# Qunyin_mmWave_flash_USB.net
KiCad netlist of a schematic drawn in Altium Designer
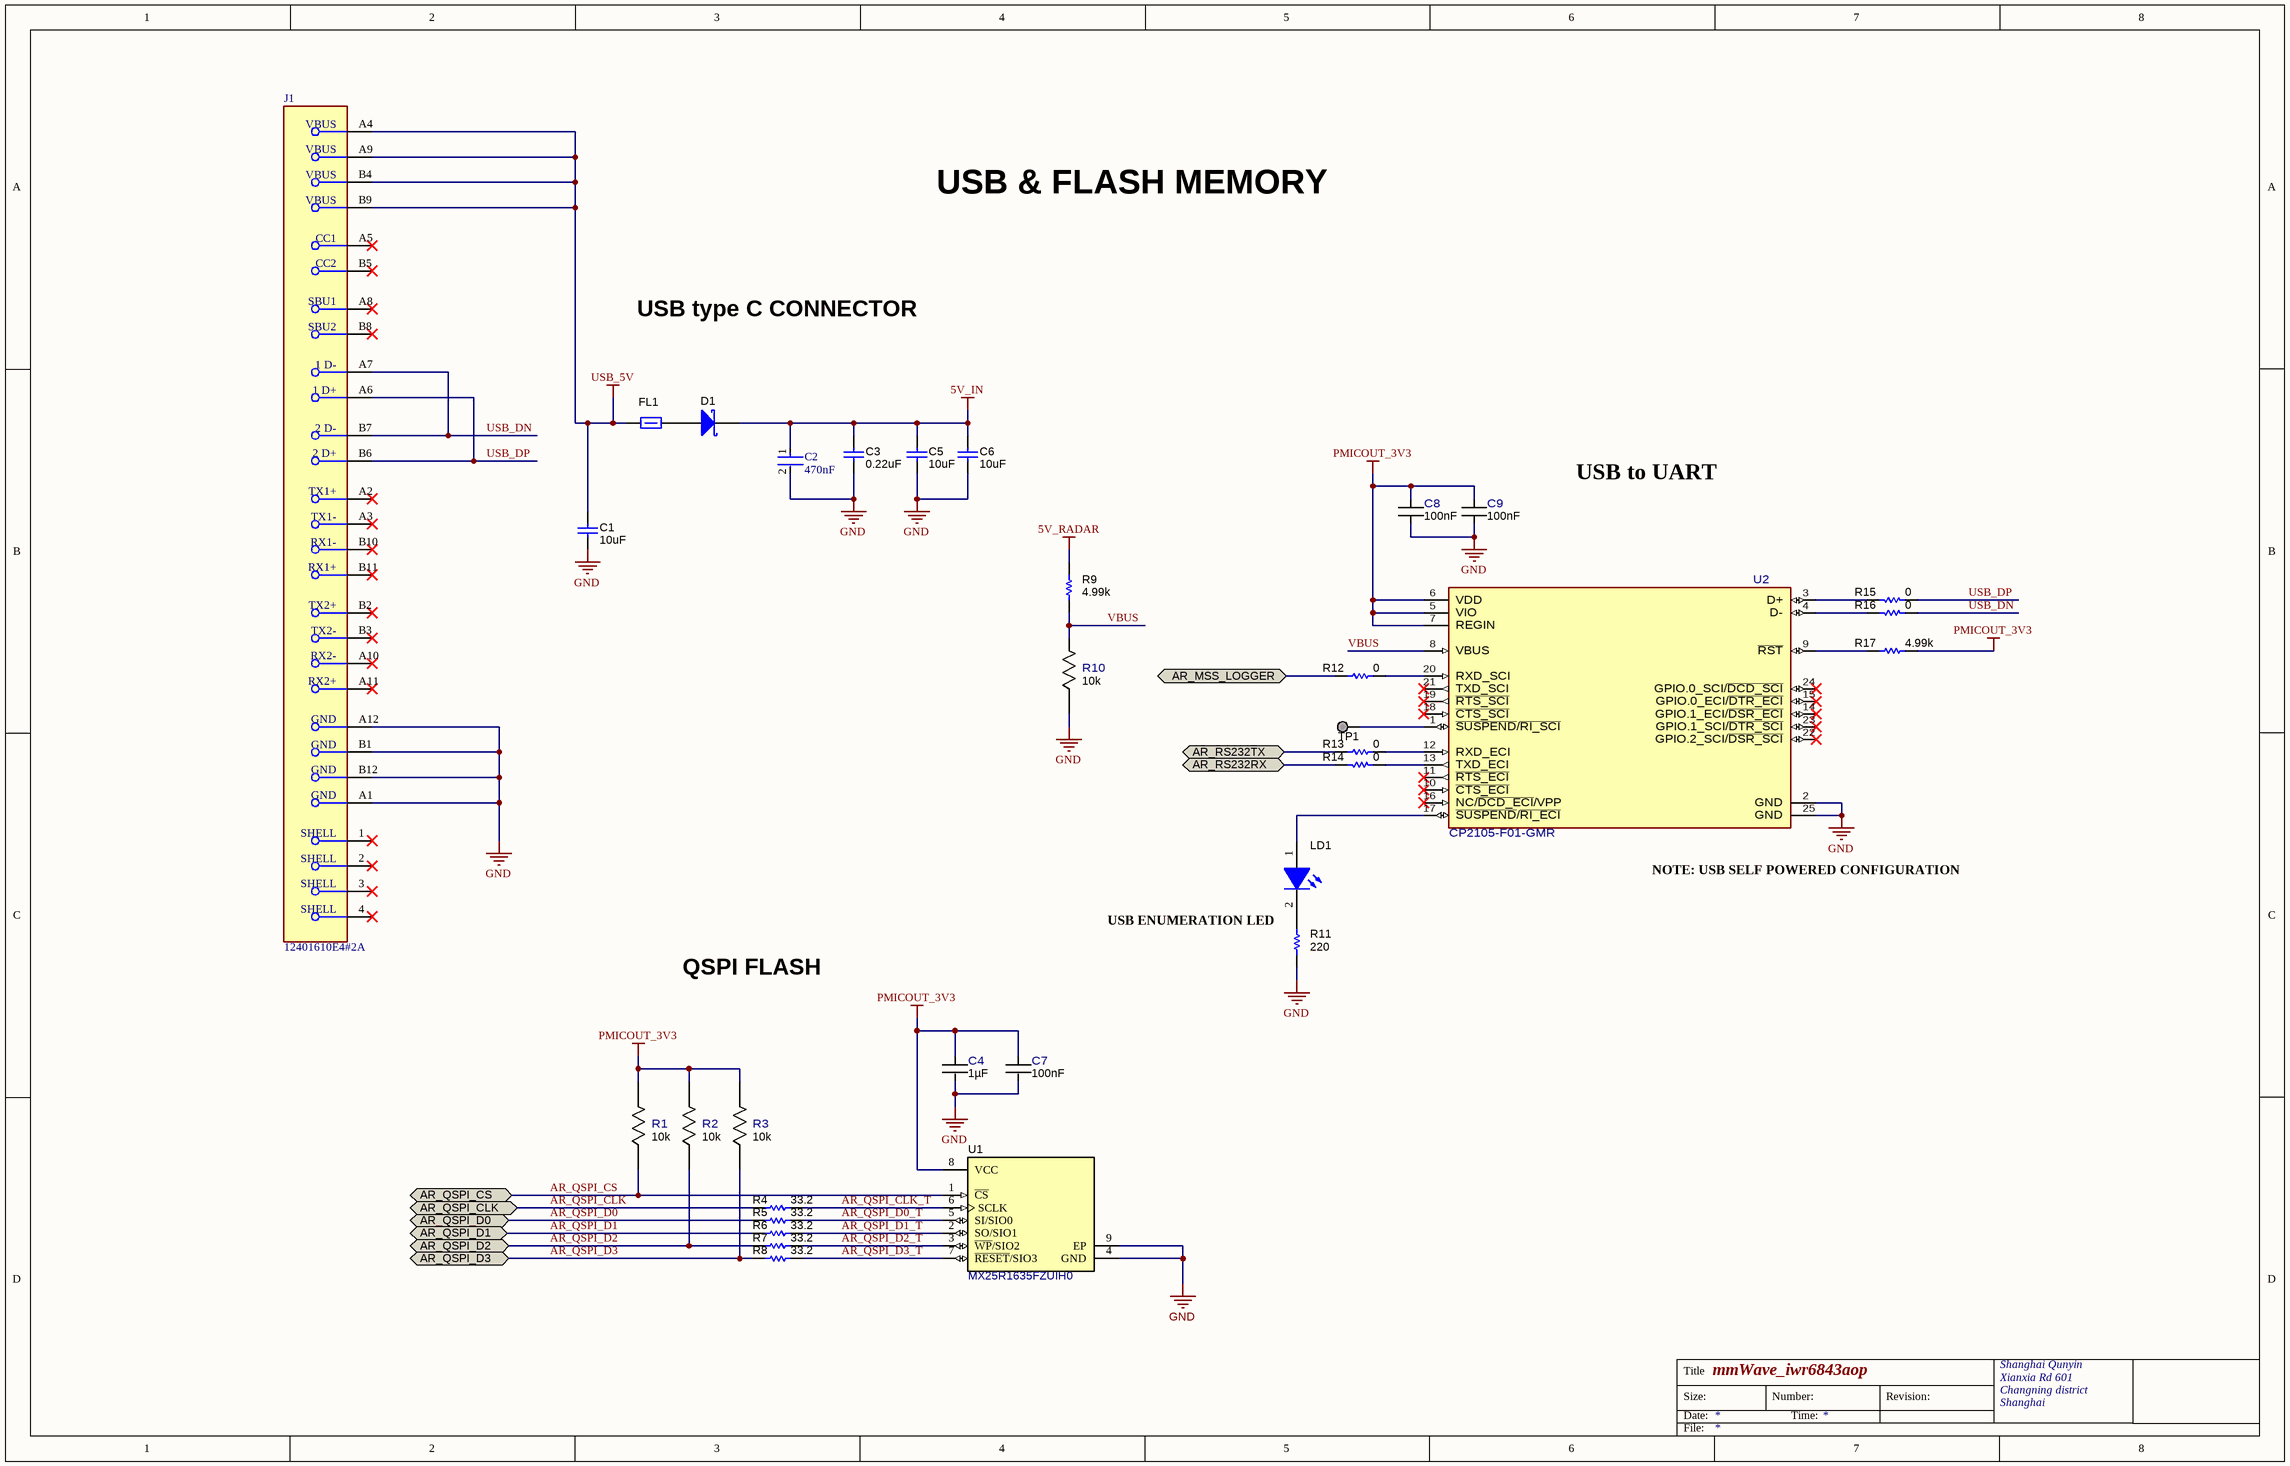
[diagram p0: Qunyin_mmWave_flash&USB.SchDoc]

(export (version "E")
  (design (tool "Eeschema 10.0.6"))
  (components
    (comp (ref "C1")
      (value "10uF")
      (footprint "0402_070")
      (description "CAP, CERM, 10 uF, 10 V, +/- 20%, X5R, 0402")
      (fields
        (field (name "MANUFACTURER") "Samsung Electro-Mechanics")
        (field (name "PARTNUMBER") "CL05A106MP5NUNC")
      )
      (libsource (lib "Altium Vault - TI") (part "Capacitor"))
    )
    (comp (ref "C2")
      (value "C1005X5R1E474K050BB")
      (footprint "FP-C1005-050-0_05-IPC_B")
      (description "Multilayer Ceramic Capacitors 470nF ±10% 25V X5R SMD 0402")
      (fields
        (field (name "VOLTAGE") "25V")
        (field (name "TOLERANCE") "10%")
        (field (name "CAPACITANCE") "470nF")
      )
      (libsource (lib "Altium Content Vault") (part "b4654b650e69147ec39a6b967a45e02"))
    )
    (comp (ref "C3")
      (value "0.22uF")
      (footprint "0201_033L")
      (description "CAP, CERM, 0.22 uF, 10 V, +/- 20%, X5R, 0201")
      (fields
        (field (name "MANUFACTURER") "Taiyo Yuden")
        (field (name "PARTNUMBER") "LMK063BJ224MP-F")
        (field (name "PUBLISHER") "Texas Instruments")
      )
      (libsource (lib "Altium Vault - TI") (part "Capacitor"))
    )
    (comp (ref "C4")
      (value "CL03A105MO3NRNH")
      (footprint "FP-CL03A105MO3NRNH_0201-IPC_C")
      (description "1µF ±20% 16V Ceramic Capacitor X5R 0201")
      (fields (field (name "CAP_F") "1µF") (field (name "MANUFACTURER") "Samsung Electro-Mechanics"))
      (libsource (lib "Altium Vault - TI") (part "SYM-B32642B0223J"))
    )
    (comp (ref "C5")
      (value "10uF")
      (footprint "0402_070")
      (description "CAP, CERM, 10 uF, 10 V, +/- 20%, X5R, 0402")
      (fields
        (field (name "MANUFACTURER") "Samsung Electro-Mechanics")
        (field (name "PARTNUMBER") "CL05A106MP5NUNC")
      )
      (libsource (lib "Altium Vault - TI") (part "Capacitor"))
    )
    (comp (ref "C6")
      (value "10uF")
      (footprint "0402_070")
      (description "CAP, CERM, 10 uF, 10 V, +/- 20%, X5R, 0402")
      (fields
        (field (name "MANUFACTURER") "Samsung Electro-Mechanics")
        (field (name "PARTNUMBER") "CL05A106MP5NUNC")
      )
      (libsource (lib "Altium Vault - TI") (part "Capacitor"))
    )
    (comp (ref "C7")
      (value "GRM033R6YA104KE14D")
      (footprint "FP-GRM033R6YA104KE14D_0201 (0603 Metric)-IPC_C")
      (description "Cap Ceramic 0.1uF 35V X5R 10% Pad SMD 0201 85C T/R")
      (fields (field (name "CAP_F") "100nF") (field (name "MANUFACTURER") "Murata Electronics North America"))
      (libsource (lib "Altium Vault - TI") (part "SYM-B32642B0223J"))
    )
    (comp (ref "C8")
      (value "GRM033R6YA104KE14D")
      (footprint "FP-GRM033R6YA104KE14D_0201 (0603 Metric)-IPC_C")
      (description "Cap Ceramic 0.1uF 35V X5R 10% Pad SMD 0201 85C T/R")
      (fields (field (name "CAP_F") "100nF") (field (name "MANUFACTURER") "Murata Electronics North America"))
      (libsource (lib "Altium Vault - TI") (part "SYM-B32642B0223J"))
    )
    (comp (ref "C9")
      (value "GRM033R6YA104KE14D")
      (footprint "FP-GRM033R6YA104KE14D_0201 (0603 Metric)-IPC_C")
      (description "Cap Ceramic 0.1uF 35V X5R 10% Pad SMD 0201 85C T/R")
      (fields (field (name "CAP_F") "100nF") (field (name "MANUFACTURER") "Murata Electronics North America"))
      (libsource (lib "Altium Vault - TI") (part "SYM-B32642B0223J"))
    )
    (comp (ref "D1")
      (value "NSR20F30NXT5G")
      (footprint "DSN2_0603")
      (description "Diode, Schottky, 30 V, 2 A, 2-XFDFN")
      (fields (field (name "MANUFACTURER") "ON Semiconductor"))
      (libsource (lib "Altium Vault - TI") (part "DIODE_SCHOTTKY"))
    )
    (comp (ref "FL1")
      (value "BLM15PD300SZ1D")
      (footprint "0402L")
      (description "Inductor, Ferrite Bead, Ferrite, 2.2 A, 0.035 ohm, AEC-Q200 Grade 1, SMD")
      (fields (field (name "MANUFACTURER") "MuRata") (field (name "PUBLISHER") "Texas Instruments"))
      (libsource (lib "Altium Vault - TI") (part "Ferrite_Bead"))
    )
    (comp (ref "J1")
      (value "12401610E4#2A")
      (footprint "FP-12401610E4#2A-MFG")
      (description "CONN RCP USB3.1 TYPEC 24P SMD RA")
      (libsource (lib "Altium Content Vault") (part "7c76f4c47d7e2af8b8797da79635f2a"))
    )
    (comp (ref "LD1")
      (value "APHHS1005CGCK")
      (footprint "APHHS1005_Green")
      (description "LED, Green, SMD")
      (fields (field (name "MANUFACTURER") "Kingbright"))
      (libsource (lib "Altium Vault - TI") (part "LED"))
    )
    (comp (ref "R1")
      (value "RR0306P-103-D")
      (footprint "FP-RR0306P-103-D_0201-IPC_C")
      (description "10 kOhms ±0.5% 0.05W, 1/20W Chip Resistor 0201 (0603 Metric)  Thin Film")
      (fields (field (name "MANUFACTURER") "Susumu") (field (name "RES_OHM") "10k"))
      (libsource (lib "Altium Vault - TI") (part "SYM-PMR18EZPJ000"))
    )
    (comp (ref "R2")
      (value "RR0306P-103-D")
      (footprint "FP-RR0306P-103-D_0201-IPC_C")
      (description "10 kOhms ±0.5% 0.05W, 1/20W Chip Resistor 0201 (0603 Metric)  Thin Film")
      (fields (field (name "MANUFACTURER") "Susumu") (field (name "RES_OHM") "10k"))
      (libsource (lib "Altium Vault - TI") (part "SYM-PMR18EZPJ000"))
    )
    (comp (ref "R3")
      (value "RR0306P-103-D")
      (footprint "FP-RR0306P-103-D_0201-IPC_C")
      (description "10 kOhms ±0.5% 0.05W, 1/20W Chip Resistor 0201 (0603 Metric)  Thin Film")
      (fields (field (name "MANUFACTURER") "Susumu") (field (name "RES_OHM") "10k"))
      (libsource (lib "Altium Vault - TI") (part "SYM-PMR18EZPJ000"))
    )
    (comp (ref "R4")
      (value "33.2")
      (footprint "0201L")
      (description "RES, 33.2, 1%, 0.05 W, 0201")
      (fields (field (name "MANUFACTURER") "Vishay-Dale") (field (name "PARTNUMBER") "CRCW020133R2FNED"))
      (libsource (lib "Altium Vault - TI") (part "Resistor"))
    )
    (comp (ref "R5")
      (value "33.2")
      (footprint "0201L")
      (description "RES, 33.2, 1%, 0.05 W, 0201")
      (fields (field (name "MANUFACTURER") "Vishay-Dale") (field (name "PARTNUMBER") "CRCW020133R2FNED"))
      (libsource (lib "Altium Vault - TI") (part "Resistor"))
    )
    (comp (ref "R6")
      (value "33.2")
      (footprint "0201L")
      (description "RES, 33.2, 1%, 0.05 W, 0201")
      (fields (field (name "MANUFACTURER") "Vishay-Dale") (field (name "PARTNUMBER") "CRCW020133R2FNED"))
      (libsource (lib "Altium Vault - TI") (part "Resistor"))
    )
    (comp (ref "R7")
      (value "33.2")
      (footprint "0201L")
      (description "RES, 33.2, 1%, 0.05 W, 0201")
      (fields (field (name "MANUFACTURER") "Vishay-Dale") (field (name "PARTNUMBER") "CRCW020133R2FNED"))
      (libsource (lib "Altium Vault - TI") (part "Resistor"))
    )
    (comp (ref "R8")
      (value "33.2")
      (footprint "0201L")
      (description "RES, 33.2, 1%, 0.05 W, 0201")
      (fields (field (name "MANUFACTURER") "Vishay-Dale") (field (name "PARTNUMBER") "CRCW020133R2FNED"))
      (libsource (lib "Altium Vault - TI") (part "Resistor"))
    )
    (comp (ref "R9")
      (value "4.99k")
      (footprint "0201L")
      (description "RES, 4.99 k, 1%, 0.05 W, 0201")
      (fields
        (field (name "MANUFACTURER") "Yageo America")
        (field (name "PARTNUMBER") "RC0201FR-074K99L")
        (field (name "PUBLISHER") "Texas Instruments")
      )
      (libsource (lib "Altium Vault - TI") (part "Resistor"))
    )
    (comp (ref "R10")
      (value "RR0306P-103-D")
      (footprint "FP-RR0306P-103-D_0201-IPC_C")
      (description "10 kOhms ±0.5% 0.05W, 1/20W Chip Resistor 0201 (0603 Metric)  Thin Film")
      (fields (field (name "MANUFACTURER") "Susumu") (field (name "RES_OHM") "10k"))
      (libsource (lib "Altium Vault - TI") (part "SYM-PMR18EZPJ000"))
    )
    (comp (ref "R11")
      (value "220")
      (footprint "0201L")
      (description "RES, 220, 5%, 0.05 W, 0201")
      (fields
        (field (name "MANUFACTURER") "Yageo America")
        (field (name "PARTNUMBER") "RC0201JR-07220RL")
        (field (name "PUBLISHER") "Texas Instruments")
      )
      (libsource (lib "Altium Vault - TI") (part "Resistor"))
    )
    (comp (ref "R12")
      (value "RC0201JR-070RL")
      (footprint "FP-RC0201JR-070RL_0201 (0603 Metric)-MFG")
      (description "RES SMD 0 OHM JUMPER 1/20W 0201")
      (fields (field (name "MANUFACTURER") "Yageo") (field (name "RES_OHM") "0"))
      (libsource (lib "Altium Vault - TI") (part "SYM-WSR3R1500F"))
    )
    (comp (ref "R13")
      (value "RC0201JR-070RL")
      (footprint "FP-RC0201JR-070RL_0201 (0603 Metric)-MFG")
      (description "RES SMD 0 OHM JUMPER 1/20W 0201")
      (fields (field (name "MANUFACTURER") "Yageo") (field (name "RES_OHM") "0"))
      (libsource (lib "Altium Vault - TI") (part "SYM-WSR3R1500F"))
    )
    (comp (ref "R14")
      (value "RC0201JR-070RL")
      (footprint "FP-RC0201JR-070RL_0201 (0603 Metric)-MFG")
      (description "RES SMD 0 OHM JUMPER 1/20W 0201")
      (fields (field (name "MANUFACTURER") "Yageo") (field (name "RES_OHM") "0"))
      (libsource (lib "Altium Vault - TI") (part "SYM-WSR3R1500F"))
    )
    (comp (ref "R15")
      (value "RC0201JR-070RL")
      (footprint "FP-RC0201JR-070RL_0201 (0603 Metric)-MFG")
      (description "RES SMD 0 OHM JUMPER 1/20W 0201")
      (fields (field (name "MANUFACTURER") "Yageo") (field (name "RES_OHM") "0"))
      (libsource (lib "Altium Vault - TI") (part "SYM-WSR3R1500F"))
    )
    (comp (ref "R16")
      (value "RC0201JR-070RL")
      (footprint "FP-RC0201JR-070RL_0201 (0603 Metric)-MFG")
      (description "RES SMD 0 OHM JUMPER 1/20W 0201")
      (fields (field (name "MANUFACTURER") "Yageo") (field (name "RES_OHM") "0"))
      (libsource (lib "Altium Vault - TI") (part "SYM-WSR3R1500F"))
    )
    (comp (ref "R17")
      (value "4.99k")
      (footprint "0201L")
      (description "RES, 4.99 k, 1%, 0.05 W, 0201")
      (fields
        (field (name "MANUFACTURER") "Yageo America")
        (field (name "PARTNUMBER") "RC0201FR-074K99L")
        (field (name "PUBLISHER") "Texas Instruments")
      )
      (libsource (lib "Altium Vault - TI") (part "Resistor"))
    )
    (comp (ref "TP1")
      (value "TESTPOINT")
      (footprint "TP_25MIL-SMT")
      (description "TEST POINT.  No entry in BOM.")
      (libsource (lib "Altium Vault - TI") (part "TESTPOINT"))
    )
    (comp (ref "U1")
      (value "MX25R1635FZUIH0")
      (footprint "USON-8L")
      (description "ULTRA LOW POWER, 16M-BIT [x 1/x 2/x 4] CMOS MXSMIO (SERIAL MULTI I/O) FLASH MEMORY, SON-8")
      (fields (field (name "MANUFACTURER") "Macronix International Co., LTD"))
      (libsource (lib "Altium Vault - TI") (part "MX25R1635FZNIH"))
    )
    (comp (ref "U2")
      (value "CP2105-F01-GMR")
      (footprint "FP-CP2105-F01-GMR_QFN24-EP-IPC_A")
      (description "I/O Controller Interface IC USB to Dual UART bridge")
      (fields (field (name "MANUFACTURER") "Silicon Labs"))
      (libsource (lib "Altium Vault - TI") (part "SYM-CP2105-F01-GMR"))
    )
  )
  (nets
    (net (code "1") (name "/AR_MSS_LOGGER") (class "Default")
      (node (ref "R12") (pin "2") (pinfunction "2_2") (pintype "passive"))
    )
    (net (code "2") (name "/AR_QSPI_CLK") (class "Default")
      (node (ref "R4") (pin "1") (pinfunction "1_1") (pintype "passive"))
    )
    (net (code "3") (name "/AR_QSPI_CLK_T") (class "Default")
      (node (ref "R4") (pin "2") (pinfunction "2_2") (pintype "passive"))
      (node (ref "U1") (pin "6") (pinfunction "SCLK_6") (pintype "input"))
    )
    (net (code "4") (name "/AR_QSPI_CS") (class "Default")
      (node (ref "R1") (pin "1") (pinfunction "1_1") (pintype "passive"))
      (node (ref "U1") (pin "1") (pinfunction "CS_1") (pintype "input"))
    )
    (net (code "5") (name "/AR_QSPI_D0") (class "Default")
      (node (ref "R5") (pin "1") (pinfunction "1_1") (pintype "passive"))
    )
    (net (code "6") (name "/AR_QSPI_D0_T") (class "Default")
      (node (ref "R5") (pin "2") (pinfunction "2_2") (pintype "passive"))
      (node (ref "U1") (pin "5") (pinfunction "SI/SIO0_5") (pintype "bidirectional"))
    )
    (net (code "7") (name "/AR_QSPI_D1") (class "Default")
      (node (ref "R6") (pin "1") (pinfunction "1_1") (pintype "passive"))
    )
    (net (code "8") (name "/AR_QSPI_D1_T") (class "Default")
      (node (ref "R6") (pin "2") (pinfunction "2_2") (pintype "passive"))
      (node (ref "U1") (pin "2") (pinfunction "SO/SIO1_2") (pintype "bidirectional"))
    )
    (net (code "9") (name "/AR_QSPI_D2") (class "Default")
      (node (ref "R2") (pin "1") (pinfunction "1_1") (pintype "passive"))
      (node (ref "R7") (pin "1") (pinfunction "1_1") (pintype "passive"))
    )
    (net (code "10") (name "/AR_QSPI_D2_T") (class "Default")
      (node (ref "R7") (pin "2") (pinfunction "2_2") (pintype "passive"))
      (node (ref "U1") (pin "3") (pinfunction "~{WP}/SIO2_3") (pintype "bidirectional"))
    )
    (net (code "11") (name "/AR_QSPI_D3") (class "Default")
      (node (ref "R3") (pin "1") (pinfunction "1_1") (pintype "passive"))
      (node (ref "R8") (pin "1") (pinfunction "1_1") (pintype "passive"))
    )
    (net (code "12") (name "/AR_QSPI_D3_T") (class "Default")
      (node (ref "R8") (pin "2") (pinfunction "2_2") (pintype "passive"))
      (node (ref "U1") (pin "7") (pinfunction "~{RESET}/SIO3_7") (pintype "bidirectional"))
    )
    (net (code "13") (name "/AR_RS232RX") (class "Default")
      (node (ref "R14") (pin "1") (pinfunction "1_1") (pintype "passive"))
    )
    (net (code "14") (name "/AR_RS232TX") (class "Default")
      (node (ref "R13") (pin "2") (pinfunction "2_2") (pintype "passive"))
    )
    (net (code "15") (name "/USB_DN") (class "Default")
      (node (ref "J1") (pin "A7") (pinfunction "1_D-_A7") (pintype "passive"))
      (node (ref "J1") (pin "B7") (pinfunction "2_D-_B7") (pintype "passive"))
      (node (ref "R16") (pin "2") (pinfunction "2_2") (pintype "passive"))
    )
    (net (code "16") (name "/USB_DP") (class "Default")
      (node (ref "J1") (pin "A6") (pinfunction "1_D+_A6") (pintype "passive"))
      (node (ref "J1") (pin "B6") (pinfunction "2_D+_B6") (pintype "passive"))
      (node (ref "R15") (pin "2") (pinfunction "2_2") (pintype "passive"))
    )
    (net (code "17") (name "/VBUS") (class "Default")
      (node (ref "R10") (pin "2") (pinfunction "2_2") (pintype "passive"))
      (node (ref "R9") (pin "2") (pinfunction "2_2") (pintype "passive"))
      (node (ref "U2") (pin "8") (pinfunction "VBUS_8") (pintype "input"))
    )
    (net (code "18") (name "5V_IN") (class "Default")
      (node (ref "C2") (pin "1") (pinfunction "1_1") (pintype "passive"))
      (node (ref "C3") (pin "1") (pinfunction "1_1") (pintype "passive"))
      (node (ref "C5") (pin "2") (pinfunction "2_2") (pintype "passive"))
      (node (ref "C6") (pin "1") (pinfunction "1_1") (pintype "passive"))
      (node (ref "D1") (pin "1") (pinfunction "K_1") (pintype "passive"))
    )
    (net (code "19") (name "5V_RADAR") (class "Default")
      (node (ref "R9") (pin "1") (pinfunction "1_1") (pintype "passive"))
    )
    (net (code "20") (name "GND") (class "Default")
      (node (ref "C1") (pin "1") (pinfunction "1_1") (pintype "passive"))
      (node (ref "C2") (pin "2") (pinfunction "2_2") (pintype "passive"))
      (node (ref "C3") (pin "2") (pinfunction "2_2") (pintype "passive"))
      (node (ref "C4") (pin "2") (pinfunction "2_2") (pintype "passive"))
      (node (ref "C5") (pin "1") (pinfunction "1_1") (pintype "passive"))
      (node (ref "C6") (pin "2") (pinfunction "2_2") (pintype "passive"))
      (node (ref "C7") (pin "2") (pinfunction "2_2") (pintype "passive"))
      (node (ref "C8") (pin "1") (pinfunction "1_1") (pintype "passive"))
      (node (ref "C9") (pin "1") (pinfunction "1_1") (pintype "passive"))
      (node (ref "J1") (pin "A1") (pinfunction "GND_A1") (pintype "power_in"))
      (node (ref "J1") (pin "A12") (pinfunction "GND_A12") (pintype "power_in"))
      (node (ref "J1") (pin "B1") (pinfunction "GND_B1") (pintype "power_in"))
      (node (ref "J1") (pin "B12") (pinfunction "GND_B12") (pintype "power_in"))
      (node (ref "R10") (pin "1") (pinfunction "1_1") (pintype "passive"))
      (node (ref "R11") (pin "1") (pinfunction "1_1") (pintype "passive"))
      (node (ref "U1") (pin "4") (pinfunction "GND_4") (pintype "power_in"))
      (node (ref "U1") (pin "9") (pinfunction "EP_9") (pintype "passive"))
      (node (ref "U2") (pin "2") (pinfunction "GND_2") (pintype "power_in"))
      (node (ref "U2") (pin "25") (pinfunction "GND_25") (pintype "power_in"))
    )
    (net (code "21") (name "Net-(D1-A)") (class "Default")
      (node (ref "D1") (pin "2") (pinfunction "A_2") (pintype "passive"))
      (node (ref "FL1") (pin "2") (pinfunction "2_2") (pintype "passive"))
    )
    (net (code "22") (name "Net-(LD1-A)") (class "Default")
      (node (ref "LD1") (pin "1") (pinfunction "A_1") (pintype "passive"))
      (node (ref "U2") (pin "17") (pinfunction "~{SUSPEND}/~{RI_ECI}_17") (pintype "bidirectional"))
    )
    (net (code "23") (name "Net-(LD1-K)") (class "Default")
      (node (ref "LD1") (pin "2") (pinfunction "K_2") (pintype "passive"))
      (node (ref "R11") (pin "2") (pinfunction "2_2") (pintype "passive"))
    )
    (net (code "24") (name "Net-(U2-D+)") (class "Default")
      (node (ref "R15") (pin "1") (pinfunction "1_1") (pintype "passive"))
      (node (ref "U2") (pin "3") (pinfunction "D+_3") (pintype "bidirectional"))
    )
    (net (code "25") (name "Net-(U2-D-)") (class "Default")
      (node (ref "R16") (pin "1") (pinfunction "1_1") (pintype "passive"))
      (node (ref "U2") (pin "4") (pinfunction "D-_4") (pintype "bidirectional"))
    )
    (net (code "26") (name "Net-(U2-RXD_ECI)") (class "Default")
      (node (ref "R13") (pin "1") (pinfunction "1_1") (pintype "passive"))
      (node (ref "U2") (pin "12") (pinfunction "RXD_ECI_12") (pintype "input"))
    )
    (net (code "27") (name "Net-(U2-RXD_SCI)") (class "Default")
      (node (ref "R12") (pin "1") (pinfunction "1_1") (pintype "passive"))
      (node (ref "U2") (pin "20") (pinfunction "RXD_SCI_20") (pintype "input"))
    )
    (net (code "28") (name "Net-(U2-TXD_ECI)") (class "Default")
      (node (ref "R14") (pin "2") (pinfunction "2_2") (pintype "passive"))
      (node (ref "U2") (pin "13") (pinfunction "TXD_ECI_13") (pintype "output"))
    )
    (net (code "29") (name "Net-(U2-~{RST})") (class "Default")
      (node (ref "R17") (pin "2") (pinfunction "2_2") (pintype "passive"))
      (node (ref "U2") (pin "9") (pinfunction "~{RST}_9") (pintype "bidirectional"))
    )
    (net (code "30") (name "Net-(U2-~{SUSPEND}{slash}~{RI_SCI})") (class "Default")
      (node (ref "TP1") (pin "1") (pintype "passive"))
      (node (ref "U2") (pin "1") (pinfunction "~{SUSPEND}/~{RI_SCI}_1") (pintype "bidirectional"))
    )
    (net (code "31") (name "PMICOUT_3V3") (class "Default")
      (node (ref "C4") (pin "1") (pinfunction "1_1") (pintype "passive"))
      (node (ref "C7") (pin "1") (pinfunction "1_1") (pintype "passive"))
      (node (ref "C8") (pin "2") (pinfunction "2_2") (pintype "passive"))
      (node (ref "C9") (pin "2") (pinfunction "2_2") (pintype "passive"))
      (node (ref "R1") (pin "2") (pinfunction "2_2") (pintype "passive"))
      (node (ref "R17") (pin "1") (pinfunction "1_1") (pintype "passive"))
      (node (ref "R2") (pin "2") (pinfunction "2_2") (pintype "passive"))
      (node (ref "R3") (pin "2") (pinfunction "2_2") (pintype "passive"))
      (node (ref "U1") (pin "8") (pinfunction "VCC_8") (pintype "power_in"))
      (node (ref "U2") (pin "5") (pinfunction "VIO_5") (pintype "power_in"))
      (node (ref "U2") (pin "6") (pinfunction "VDD_6") (pintype "power_in"))
      (node (ref "U2") (pin "7") (pinfunction "REGIN_7") (pintype "power_in"))
    )
    (net (code "32") (name "USB_5V") (class "Default")
      (node (ref "C1") (pin "2") (pinfunction "2_2") (pintype "passive"))
      (node (ref "FL1") (pin "1") (pinfunction "1_1") (pintype "passive"))
      (node (ref "J1") (pin "A4") (pinfunction "VBUS_A4") (pintype "power_in"))
      (node (ref "J1") (pin "A9") (pinfunction "VBUS_A9") (pintype "power_in"))
      (node (ref "J1") (pin "B4") (pinfunction "VBUS_B4") (pintype "power_in"))
      (node (ref "J1") (pin "B9") (pinfunction "VBUS_B9") (pintype "power_in"))
    )
    (net (code "33") (name "unconnected-(J1-CC1-PadA5)") (class "Default")
      (node (ref "J1") (pin "A5") (pinfunction "CC1_A5") (pintype "passive+no_connect"))
    )
    (net (code "34") (name "unconnected-(J1-CC2-PadB5)") (class "Default")
      (node (ref "J1") (pin "B5") (pinfunction "CC2_B5") (pintype "passive+no_connect"))
    )
    (net (code "35") (name "unconnected-(J1-RX1+-PadB11)") (class "Default")
      (node (ref "J1") (pin "B11") (pinfunction "RX1+_B11") (pintype "passive+no_connect"))
    )
    (net (code "36") (name "unconnected-(J1-RX1--PadB10)") (class "Default")
      (node (ref "J1") (pin "B10") (pinfunction "RX1-_B10") (pintype "passive+no_connect"))
    )
    (net (code "37") (name "unconnected-(J1-RX2+-PadA11)") (class "Default")
      (node (ref "J1") (pin "A11") (pinfunction "RX2+_A11") (pintype "passive+no_connect"))
    )
    (net (code "38") (name "unconnected-(J1-RX2--PadA10)") (class "Default")
      (node (ref "J1") (pin "A10") (pinfunction "RX2-_A10") (pintype "passive+no_connect"))
    )
    (net (code "39") (name "unconnected-(J1-SBU1-PadA8)") (class "Default")
      (node (ref "J1") (pin "A8") (pinfunction "SBU1_A8") (pintype "passive+no_connect"))
    )
    (net (code "40") (name "unconnected-(J1-SBU2-PadB8)") (class "Default")
      (node (ref "J1") (pin "B8") (pinfunction "SBU2_B8") (pintype "passive+no_connect"))
    )
    (net (code "41") (name "unconnected-(J1-SHELL-Pad1)") (class "Default")
      (node (ref "J1") (pin "1") (pinfunction "SHELL_1") (pintype "power_in+no_connect"))
    )
    (net (code "42") (name "unconnected-(J1-SHELL-Pad2)") (class "Default")
      (node (ref "J1") (pin "2") (pinfunction "SHELL_2") (pintype "power_in+no_connect"))
    )
    (net (code "43") (name "unconnected-(J1-SHELL-Pad3)") (class "Default")
      (node (ref "J1") (pin "3") (pinfunction "SHELL_3") (pintype "power_in+no_connect"))
    )
    (net (code "44") (name "unconnected-(J1-SHELL-Pad4)") (class "Default")
      (node (ref "J1") (pin "4") (pinfunction "SHELL_4") (pintype "power_in+no_connect"))
    )
    (net (code "45") (name "unconnected-(J1-TX1+-PadA2)") (class "Default")
      (node (ref "J1") (pin "A2") (pinfunction "TX1+_A2") (pintype "passive+no_connect"))
    )
    (net (code "46") (name "unconnected-(J1-TX1--PadA3)") (class "Default")
      (node (ref "J1") (pin "A3") (pinfunction "TX1-_A3") (pintype "passive+no_connect"))
    )
    (net (code "47") (name "unconnected-(J1-TX2+-PadB2)") (class "Default")
      (node (ref "J1") (pin "B2") (pinfunction "TX2+_B2") (pintype "passive+no_connect"))
    )
    (net (code "48") (name "unconnected-(J1-TX2--PadB3)") (class "Default")
      (node (ref "J1") (pin "B3") (pinfunction "TX2-_B3") (pintype "passive+no_connect"))
    )
    (net (code "49") (name "unconnected-(U2-GPIO.0_ECI{slash}~{DTR_ECI}-Pad15)") (class "Default")
      (node (ref "U2") (pin "15") (pinfunction "GPIO.0_ECI/~{DTR_ECI}_15") (pintype "bidirectional+no_connect"))
    )
    (net (code "50") (name "unconnected-(U2-GPIO.0_SCI{slash}~{DCD_SCI}-Pad24)") (class "Default")
      (node (ref "U2") (pin "24") (pinfunction "GPIO.0_SCI/~{DCD_SCI}_24") (pintype "bidirectional+no_connect"))
    )
    (net (code "51") (name "unconnected-(U2-GPIO.1_ECI{slash}~{DSR_ECI}-Pad14)") (class "Default")
      (node (ref "U2") (pin "14") (pinfunction "GPIO.1_ECI/~{DSR_ECI}_14") (pintype "bidirectional+no_connect"))
    )
    (net (code "52") (name "unconnected-(U2-GPIO.1_SCI{slash}~{DTR_SCI}-Pad23)") (class "Default")
      (node (ref "U2") (pin "23") (pinfunction "GPIO.1_SCI/~{DTR_SCI}_23") (pintype "bidirectional+no_connect"))
    )
    (net (code "53") (name "unconnected-(U2-GPIO.2_SCI{slash}~{DSR_SCI}-Pad22)") (class "Default")
      (node (ref "U2") (pin "22") (pinfunction "GPIO.2_SCI/~{DSR_SCI}_22") (pintype "bidirectional+no_connect"))
    )
    (net (code "54") (name "unconnected-(U2-NC{slash}~{DCD_ECI}{slash}VPP-Pad16)") (class "Default")
      (node (ref "U2") (pin "16") (pinfunction "NC/~{DCD_ECI}/VPP_16") (pintype "input+no_connect"))
    )
    (net (code "55") (name "unconnected-(U2-TXD_SCI-Pad21)") (class "Default")
      (node (ref "U2") (pin "21") (pinfunction "TXD_SCI_21") (pintype "output+no_connect"))
    )
    (net (code "56") (name "unconnected-(U2-~{CTS_ECI}-Pad10)") (class "Default")
      (node (ref "U2") (pin "10") (pinfunction "~{CTS_ECI}_10") (pintype "input+no_connect"))
    )
    (net (code "57") (name "unconnected-(U2-~{CTS_SCI}-Pad18)") (class "Default")
      (node (ref "U2") (pin "18") (pinfunction "~{CTS_SCI}_18") (pintype "input+no_connect"))
    )
    (net (code "58") (name "unconnected-(U2-~{RTS_ECI}-Pad11)") (class "Default")
      (node (ref "U2") (pin "11") (pinfunction "~{RTS_ECI}_11") (pintype "output+no_connect"))
    )
    (net (code "59") (name "unconnected-(U2-~{RTS_SCI}-Pad19)") (class "Default")
      (node (ref "U2") (pin "19") (pinfunction "~{RTS_SCI}_19") (pintype "output+no_connect"))
    )
  )
)
